# quad2.net
KiCad netlist of a schematic drawn in EAGLE
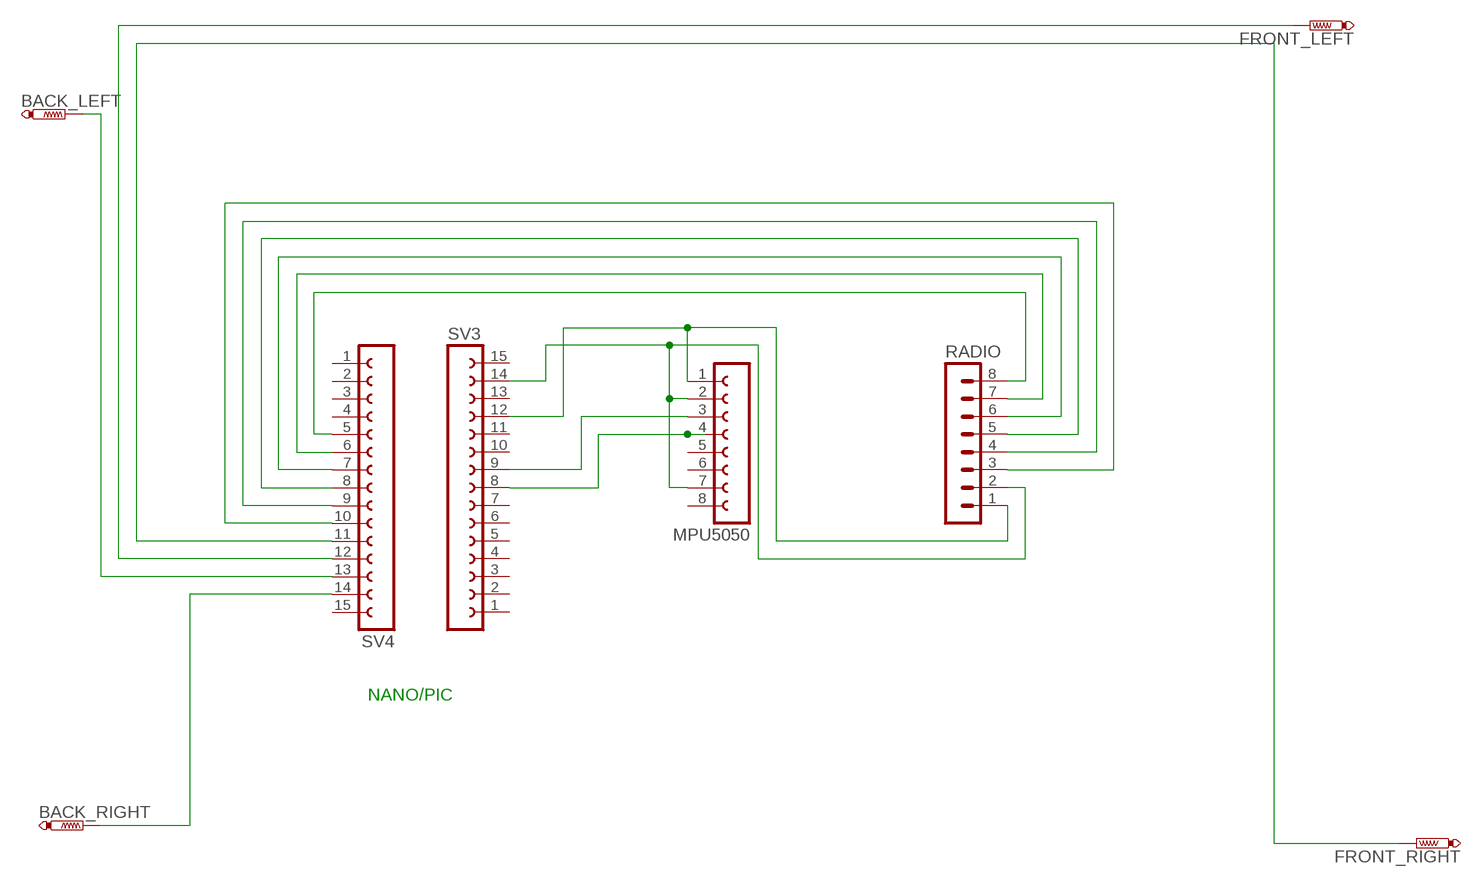
[diagram p0: schematic, sheet 1]

(export (version "E")
  (design (tool "Eeschema 10.0.6"))
  (components
    (comp (ref "BACK_LEFT")
      (value "PTR1PAD1-13Y")
      (footprint "eagle-import:P1-13Y")
      (libsource (lib "eagle-import") (part "PTR1PAD1-13Y"))
    )
    (comp (ref "BACK_RIGHT")
      (value "PTR1PAD1-13Y")
      (footprint "eagle-import:P1-13Y")
      (libsource (lib "eagle-import") (part "PTR1PAD1-13Y"))
    )
    (comp (ref "FRONT_LEFT")
      (value "PTR1PAD1-13Y")
      (footprint "eagle-import:P1-13Y")
      (libsource (lib "eagle-import") (part "PTR1PAD1-13Y"))
    )
    (comp (ref "FRONT_RIGHT")
      (value "PTR1PAD1-13Y")
      (footprint "eagle-import:P1-13Y")
      (libsource (lib "eagle-import") (part "PTR1PAD1-13Y"))
    )
    (comp (ref "MPU5050")
      (value "FE08-1")
      (footprint "eagle-import:FE08")
      (libsource (lib "eagle-import") (part "FE08-1"))
    )
    (comp (ref "RADIO")
      (value "MA08-1")
      (footprint "eagle-import:MA08-1")
      (libsource (lib "eagle-import") (part "MA08-1"))
    )
    (comp (ref "SV3")
      (value "FE15-1")
      (footprint "eagle-import:FE15")
      (libsource (lib "eagle-import") (part "FE15-1"))
    )
    (comp (ref "SV4")
      (value "FE15-1")
      (footprint "eagle-import:FE15")
      (libsource (lib "eagle-import") (part "FE15-1"))
    )
  )
  (nets
    (net (code "1") (name "Net-(BACK_LEFT-PadTP)") (class "Default")
      (node (ref "BACK_LEFT") (pin "TP") (pinfunction "TP_TP") (pintype "input"))
      (node (ref "SV4") (pin "13") (pinfunction "13_13") (pintype "passive"))
    )
    (net (code "2") (name "Net-(BACK_RIGHT-PadTP)") (class "Default")
      (node (ref "BACK_RIGHT") (pin "TP") (pinfunction "TP_TP") (pintype "input"))
      (node (ref "SV4") (pin "14") (pinfunction "14_14") (pintype "passive"))
    )
    (net (code "3") (name "Net-(FRONT_LEFT-PadTP)") (class "Default")
      (node (ref "FRONT_LEFT") (pin "TP") (pinfunction "TP_TP") (pintype "input"))
      (node (ref "SV4") (pin "12") (pinfunction "12_12") (pintype "passive"))
    )
    (net (code "4") (name "Net-(FRONT_RIGHT-PadTP)") (class "Default")
      (node (ref "FRONT_RIGHT") (pin "TP") (pinfunction "TP_TP") (pintype "input"))
      (node (ref "SV4") (pin "11") (pinfunction "11_11") (pintype "passive"))
    )
    (net (code "5") (name "Net-(MPU5050-Pad1)") (class "Default")
      (node (ref "MPU5050") (pin "1") (pinfunction "1_1") (pintype "passive"))
      (node (ref "RADIO") (pin "1") (pinfunction "1_1") (pintype "passive"))
      (node (ref "SV3") (pin "12") (pinfunction "12_12") (pintype "passive"))
    )
    (net (code "6") (name "Net-(MPU5050-Pad2)") (class "Default")
      (node (ref "MPU5050") (pin "2") (pinfunction "2_2") (pintype "passive"))
      (node (ref "MPU5050") (pin "7") (pinfunction "7_7") (pintype "passive"))
      (node (ref "RADIO") (pin "2") (pinfunction "2_2") (pintype "passive"))
      (node (ref "SV3") (pin "14") (pinfunction "14_14") (pintype "passive"))
    )
    (net (code "7") (name "Net-(MPU5050-Pad3)") (class "Default")
      (node (ref "MPU5050") (pin "3") (pinfunction "3_3") (pintype "passive"))
      (node (ref "SV3") (pin "9") (pinfunction "9_9") (pintype "passive"))
    )
    (net (code "8") (name "Net-(MPU5050-Pad4)") (class "Default")
      (node (ref "MPU5050") (pin "4") (pinfunction "4_4") (pintype "passive"))
      (node (ref "SV3") (pin "8") (pinfunction "8_8") (pintype "passive"))
    )
    (net (code "9") (name "Net-(RADIO-Pad3)") (class "Default")
      (node (ref "RADIO") (pin "3") (pinfunction "3_3") (pintype "passive"))
      (node (ref "SV4") (pin "10") (pinfunction "10_10") (pintype "passive"))
    )
    (net (code "10") (name "Net-(RADIO-Pad4)") (class "Default")
      (node (ref "RADIO") (pin "4") (pinfunction "4_4") (pintype "passive"))
      (node (ref "SV4") (pin "9") (pinfunction "9_9") (pintype "passive"))
    )
    (net (code "11") (name "Net-(RADIO-Pad5)") (class "Default")
      (node (ref "RADIO") (pin "5") (pinfunction "5_5") (pintype "passive"))
      (node (ref "SV4") (pin "8") (pinfunction "8_8") (pintype "passive"))
    )
    (net (code "12") (name "Net-(RADIO-Pad6)") (class "Default")
      (node (ref "RADIO") (pin "6") (pinfunction "6_6") (pintype "passive"))
      (node (ref "SV4") (pin "7") (pinfunction "7_7") (pintype "passive"))
    )
    (net (code "13") (name "Net-(RADIO-Pad7)") (class "Default")
      (node (ref "RADIO") (pin "7") (pinfunction "7_7") (pintype "passive"))
      (node (ref "SV4") (pin "6") (pinfunction "6_6") (pintype "passive"))
    )
    (net (code "14") (name "Net-(RADIO-Pad8)") (class "Default")
      (node (ref "RADIO") (pin "8") (pinfunction "8_8") (pintype "passive"))
      (node (ref "SV4") (pin "5") (pinfunction "5_5") (pintype "passive"))
    )
    (net (code "15") (name "unconnected-(MPU5050-Pad5)") (class "Default")
      (node (ref "MPU5050") (pin "5") (pinfunction "5_5") (pintype "passive"))
    )
    (net (code "16") (name "unconnected-(MPU5050-Pad6)") (class "Default")
      (node (ref "MPU5050") (pin "6") (pinfunction "6_6") (pintype "passive"))
    )
    (net (code "17") (name "unconnected-(MPU5050-Pad8)") (class "Default")
      (node (ref "MPU5050") (pin "8") (pinfunction "8_8") (pintype "passive"))
    )
    (net (code "18") (name "unconnected-(SV3-Pad1)") (class "Default")
      (node (ref "SV3") (pin "1") (pinfunction "1_1") (pintype "passive"))
    )
    (net (code "19") (name "unconnected-(SV3-Pad2)") (class "Default")
      (node (ref "SV3") (pin "2") (pinfunction "2_2") (pintype "passive"))
    )
    (net (code "20") (name "unconnected-(SV3-Pad3)") (class "Default")
      (node (ref "SV3") (pin "3") (pinfunction "3_3") (pintype "passive"))
    )
    (net (code "21") (name "unconnected-(SV3-Pad4)") (class "Default")
      (node (ref "SV3") (pin "4") (pinfunction "4_4") (pintype "passive"))
    )
    (net (code "22") (name "unconnected-(SV3-Pad5)") (class "Default")
      (node (ref "SV3") (pin "5") (pinfunction "5_5") (pintype "passive"))
    )
    (net (code "23") (name "unconnected-(SV3-Pad6)") (class "Default")
      (node (ref "SV3") (pin "6") (pinfunction "6_6") (pintype "passive"))
    )
    (net (code "24") (name "unconnected-(SV3-Pad7)") (class "Default")
      (node (ref "SV3") (pin "7") (pinfunction "7_7") (pintype "passive"))
    )
    (net (code "25") (name "unconnected-(SV3-Pad10)") (class "Default")
      (node (ref "SV3") (pin "10") (pinfunction "10_10") (pintype "passive"))
    )
    (net (code "26") (name "unconnected-(SV3-Pad11)") (class "Default")
      (node (ref "SV3") (pin "11") (pinfunction "11_11") (pintype "passive"))
    )
    (net (code "27") (name "unconnected-(SV3-Pad13)") (class "Default")
      (node (ref "SV3") (pin "13") (pinfunction "13_13") (pintype "passive"))
    )
    (net (code "28") (name "unconnected-(SV3-Pad15)") (class "Default")
      (node (ref "SV3") (pin "15") (pinfunction "15_15") (pintype "passive"))
    )
    (net (code "29") (name "unconnected-(SV4-Pad1)") (class "Default")
      (node (ref "SV4") (pin "1") (pinfunction "1_1") (pintype "passive"))
    )
    (net (code "30") (name "unconnected-(SV4-Pad2)") (class "Default")
      (node (ref "SV4") (pin "2") (pinfunction "2_2") (pintype "passive"))
    )
    (net (code "31") (name "unconnected-(SV4-Pad3)") (class "Default")
      (node (ref "SV4") (pin "3") (pinfunction "3_3") (pintype "passive"))
    )
    (net (code "32") (name "unconnected-(SV4-Pad4)") (class "Default")
      (node (ref "SV4") (pin "4") (pinfunction "4_4") (pintype "passive"))
    )
    (net (code "33") (name "unconnected-(SV4-Pad15)") (class "Default")
      (node (ref "SV4") (pin "15") (pinfunction "15_15") (pintype "passive"))
    )
  )
)
